# md_builtin_game_v14.net
KiCad netlist of a schematic drawn in EAGLE
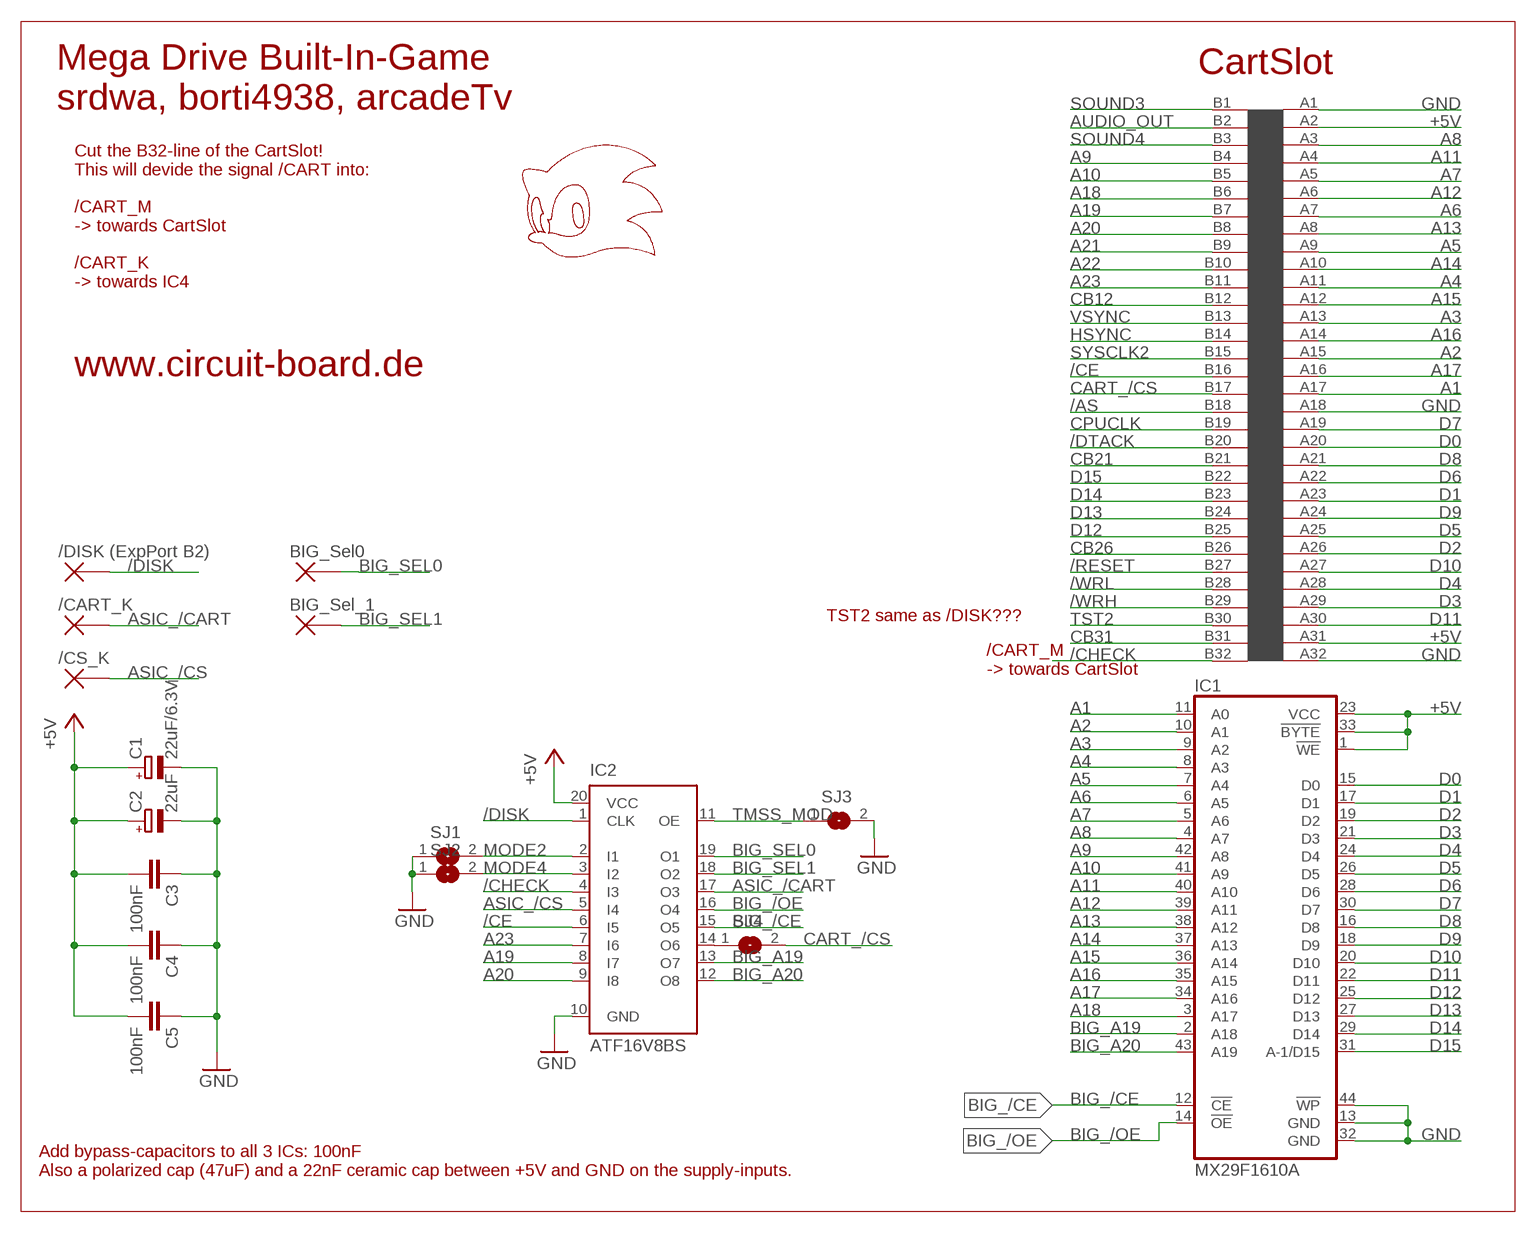
[diagram p0: schematic, sheet 1]

(export (version "E")
  (design (tool "Eeschema 10.0.6"))
  (components
    (comp (ref "C1")
      (value "22uF/6.3V")
      (footprint "eagle-import:SMC_B")
      (libsource (lib "eagle-import") (part "CPOL-EUSMCB"))
    )
    (comp (ref "C2")
      (value "22uF")
      (footprint "eagle-import:SMC_B")
      (libsource (lib "eagle-import") (part "CPOL-EUSMCB"))
    )
    (comp (ref "C3")
      (value "100nF")
      (footprint "eagle-import:Z0805")
      (libsource (lib "eagle-import") (part "C0805"))
    )
    (comp (ref "C4")
      (value "100nF")
      (footprint "eagle-import:Z0805")
      (libsource (lib "eagle-import") (part "C0805"))
    )
    (comp (ref "C5")
      (value "100nF")
      (footprint "eagle-import:Z0805")
      (libsource (lib "eagle-import") (part "C0805"))
    )
    (comp (ref "IC1")
      (value "MX29F1610A")
      (footprint "eagle-import:SO44")
      (libsource (lib "eagle-import") (part "MX29F1610A"))
    )
    (comp (ref "IC2")
      (value "ATF16V8BS")
      (footprint "eagle-import:SO20L")
      (libsource (lib "eagle-import") (part "ATF16V8BS"))
    )
    (comp (ref "SJ1") (value "SJ") (footprint "eagle-import:SJ") (libsource (lib "eagle-import") (part "SJ")))
    (comp (ref "SJ2") (value "SJ") (footprint "eagle-import:SJ") (libsource (lib "eagle-import") (part "SJ")))
    (comp (ref "SJ3") (value "SJ") (footprint "eagle-import:SJ") (libsource (lib "eagle-import") (part "SJ")))
    (comp (ref "SJ4") (value "SJ") (footprint "eagle-import:SJ") (libsource (lib "eagle-import") (part "SJ")))
    (comp (ref "U$1")
      (value "LOGO_SONIC_20MM")
      (footprint "eagle-import:LOGO_SONIC_20MM")
      (libsource (lib "eagle-import") (part "LOGO_SONIC_20MM"))
    )
    (comp (ref "U$2")
      (value "/CS_K")
      (footprint "eagle-import:PADS")
      (libsource (lib "eagle-import") (part "PAD"))
    )
    (comp (ref "U$3")
      (value "/CART_K")
      (footprint "eagle-import:PADS")
      (libsource (lib "eagle-import") (part "PAD"))
    )
    (comp (ref "U$4")
      (value "/DISK (ExpPort B2)")
      (footprint "eagle-import:PADS")
      (libsource (lib "eagle-import") (part "PAD"))
    )
    (comp (ref "U$5")
      (value "BIG_Sel0")
      (footprint "eagle-import:PADS")
      (libsource (lib "eagle-import") (part "PAD"))
    )
    (comp (ref "U$6")
      (value "MEGADRIVE_EDGE_CONNECTOR")
      (footprint "eagle-import:MEGADRIVE_EDGE_CONNECTOR")
      (libsource (lib "eagle-import") (part "MEGADRIVE_EDGE_CONNECTOR"))
    )
    (comp (ref "U$7")
      (value "BIG_Sel_1")
      (footprint "eagle-import:PADS")
      (libsource (lib "eagle-import") (part "PAD"))
    )
  )
  (nets
    (net (code "1") (name "+5V") (class "Default")
      (node (ref "C1") (pin "+") (pinfunction "+_+") (pintype "passive"))
      (node (ref "C2") (pin "+") (pinfunction "+_+") (pintype "passive"))
      (node (ref "C3") (pin "2") (pinfunction "2_2") (pintype "passive"))
      (node (ref "C4") (pin "2") (pinfunction "2_2") (pintype "passive"))
      (node (ref "C5") (pin "2") (pinfunction "2_2") (pintype "passive"))
      (node (ref "IC1") (pin "1") (pinfunction "~{WE}_1") (pintype "input"))
      (node (ref "IC1") (pin "23") (pinfunction "VCC_23") (pintype "output"))
      (node (ref "IC1") (pin "33") (pinfunction "~{BYTE}_33") (pintype "input"))
      (node (ref "IC2") (pin "20") (pinfunction "VCC_20") (pintype "power_in"))
      (node (ref "U$6") (pin "A2") (pinfunction "A2_A2") (pintype "bidirectional"))
      (node (ref "U$6") (pin "A31") (pinfunction "A31_A31") (pintype "bidirectional"))
    )
    (net (code "2") (name "/A1") (class "Default")
      (node (ref "IC1") (pin "11") (pinfunction "A0_11") (pintype "input"))
      (node (ref "U$6") (pin "A17") (pinfunction "A17_A17") (pintype "bidirectional"))
    )
    (net (code "3") (name "/A2") (class "Default")
      (node (ref "IC1") (pin "10") (pinfunction "A1_10") (pintype "input"))
      (node (ref "U$6") (pin "A15") (pinfunction "A15_A15") (pintype "bidirectional"))
    )
    (net (code "4") (name "/A3") (class "Default")
      (node (ref "IC1") (pin "9") (pinfunction "A2_9") (pintype "input"))
      (node (ref "U$6") (pin "A13") (pinfunction "A13_A13") (pintype "bidirectional"))
    )
    (net (code "5") (name "/A4") (class "Default")
      (node (ref "IC1") (pin "8") (pinfunction "A3_8") (pintype "input"))
      (node (ref "U$6") (pin "A11") (pinfunction "A11_A11") (pintype "bidirectional"))
    )
    (net (code "6") (name "/A5") (class "Default")
      (node (ref "IC1") (pin "7") (pinfunction "A4_7") (pintype "input"))
      (node (ref "U$6") (pin "A9") (pinfunction "A9_A9") (pintype "bidirectional"))
    )
    (net (code "7") (name "/A6") (class "Default")
      (node (ref "IC1") (pin "6") (pinfunction "A5_6") (pintype "input"))
      (node (ref "U$6") (pin "A7") (pinfunction "A7_A7") (pintype "bidirectional"))
    )
    (net (code "8") (name "/A7") (class "Default")
      (node (ref "IC1") (pin "5") (pinfunction "A6_5") (pintype "input"))
      (node (ref "U$6") (pin "A5") (pinfunction "A5_A5") (pintype "bidirectional"))
    )
    (net (code "9") (name "/A8") (class "Default")
      (node (ref "IC1") (pin "4") (pinfunction "A7_4") (pintype "input"))
      (node (ref "U$6") (pin "A3") (pinfunction "A3_A3") (pintype "bidirectional"))
    )
    (net (code "10") (name "/A9") (class "Default")
      (node (ref "IC1") (pin "42") (pinfunction "A8_42") (pintype "input"))
      (node (ref "U$6") (pin "B4") (pinfunction "B4_B4") (pintype "bidirectional"))
    )
    (net (code "11") (name "/A10") (class "Default")
      (node (ref "IC1") (pin "41") (pinfunction "A9_41") (pintype "input"))
      (node (ref "U$6") (pin "B5") (pinfunction "B5_B5") (pintype "bidirectional"))
    )
    (net (code "12") (name "/A11") (class "Default")
      (node (ref "IC1") (pin "40") (pinfunction "A10_40") (pintype "input"))
      (node (ref "U$6") (pin "A4") (pinfunction "A4_A4") (pintype "bidirectional"))
    )
    (net (code "13") (name "/A12") (class "Default")
      (node (ref "IC1") (pin "39") (pinfunction "A11_39") (pintype "input"))
      (node (ref "U$6") (pin "A6") (pinfunction "A6_A6") (pintype "bidirectional"))
    )
    (net (code "14") (name "/A13") (class "Default")
      (node (ref "IC1") (pin "38") (pinfunction "A12_38") (pintype "input"))
      (node (ref "U$6") (pin "A8") (pinfunction "A8_A8") (pintype "bidirectional"))
    )
    (net (code "15") (name "/A14") (class "Default")
      (node (ref "IC1") (pin "37") (pinfunction "A13_37") (pintype "input"))
      (node (ref "U$6") (pin "A10") (pinfunction "A10_A10") (pintype "bidirectional"))
    )
    (net (code "16") (name "/A15") (class "Default")
      (node (ref "IC1") (pin "36") (pinfunction "A14_36") (pintype "input"))
      (node (ref "U$6") (pin "A12") (pinfunction "A12_A12") (pintype "bidirectional"))
    )
    (net (code "17") (name "/A16") (class "Default")
      (node (ref "IC1") (pin "35") (pinfunction "A15_35") (pintype "input"))
      (node (ref "U$6") (pin "A14") (pinfunction "A14_A14") (pintype "bidirectional"))
    )
    (net (code "18") (name "/A17") (class "Default")
      (node (ref "IC1") (pin "34") (pinfunction "A16_34") (pintype "input"))
      (node (ref "U$6") (pin "A16") (pinfunction "A16_A16") (pintype "bidirectional"))
    )
    (net (code "19") (name "/A18") (class "Default")
      (node (ref "IC1") (pin "3") (pinfunction "A17_3") (pintype "input"))
      (node (ref "U$6") (pin "B6") (pinfunction "B6_B6") (pintype "bidirectional"))
    )
    (net (code "20") (name "/A19") (class "Default")
      (node (ref "IC2") (pin "8") (pinfunction "I7_8") (pintype "input"))
      (node (ref "U$6") (pin "B7") (pinfunction "B7_B7") (pintype "bidirectional"))
    )
    (net (code "21") (name "/A20") (class "Default")
      (node (ref "IC2") (pin "9") (pinfunction "I8_9") (pintype "input"))
      (node (ref "U$6") (pin "B8") (pinfunction "B8_B8") (pintype "bidirectional"))
    )
    (net (code "22") (name "/A21") (class "Default")
      (node (ref "U$6") (pin "B9") (pinfunction "B9_B9") (pintype "bidirectional"))
    )
    (net (code "23") (name "/A22") (class "Default")
      (node (ref "U$6") (pin "B10") (pinfunction "B10_B10") (pintype "bidirectional"))
    )
    (net (code "24") (name "/A23") (class "Default")
      (node (ref "IC2") (pin "7") (pinfunction "I6_7") (pintype "input"))
      (node (ref "U$6") (pin "B11") (pinfunction "B11_B11") (pintype "bidirectional"))
    )
    (net (code "25") (name "/ASIC_{slash}CART") (class "Default")
      (node (ref "IC2") (pin "17") (pinfunction "O3_17") (pintype "output"))
      (node (ref "U$3") (pin "P$1") (pinfunction "P$1_P$1") (pintype "bidirectional"))
    )
    (net (code "26") (name "/ASIC_{slash}CS") (class "Default")
      (node (ref "IC2") (pin "5") (pinfunction "I4_5") (pintype "input"))
      (node (ref "U$2") (pin "P$1") (pinfunction "P$1_P$1") (pintype "bidirectional"))
    )
    (net (code "27") (name "/AUDIO_OUT") (class "Default")
      (node (ref "U$6") (pin "B2") (pinfunction "B2_B2") (pintype "bidirectional"))
    )
    (net (code "28") (name "/BIG_A19") (class "Default")
      (node (ref "IC1") (pin "2") (pinfunction "A18_2") (pintype "input"))
      (node (ref "IC2") (pin "13") (pinfunction "O7_13") (pintype "output"))
    )
    (net (code "29") (name "/BIG_A20") (class "Default")
      (node (ref "IC1") (pin "43") (pinfunction "A19_43") (pintype "input"))
      (node (ref "IC2") (pin "12") (pinfunction "O8_12") (pintype "output"))
    )
    (net (code "30") (name "/BIG_SEL0") (class "Default")
      (node (ref "IC2") (pin "19") (pinfunction "O1_19") (pintype "output"))
      (node (ref "U$5") (pin "P$1") (pinfunction "P$1_P$1") (pintype "bidirectional"))
    )
    (net (code "31") (name "/BIG_SEL1") (class "Default")
      (node (ref "IC2") (pin "18") (pinfunction "O2_18") (pintype "output"))
      (node (ref "U$7") (pin "P$1") (pinfunction "P$1_P$1") (pintype "bidirectional"))
    )
    (net (code "32") (name "/CART_{slash}CS") (class "Default")
      (node (ref "SJ4") (pin "2") (pinfunction "2_2") (pintype "passive"))
      (node (ref "U$6") (pin "B17") (pinfunction "B17_B17") (pintype "bidirectional"))
    )
    (net (code "33") (name "/CB12") (class "Default")
      (node (ref "U$6") (pin "B12") (pinfunction "B12_B12") (pintype "bidirectional"))
    )
    (net (code "34") (name "/CB21") (class "Default")
      (node (ref "U$6") (pin "B21") (pinfunction "B21_B21") (pintype "bidirectional"))
    )
    (net (code "35") (name "/CB26") (class "Default")
      (node (ref "U$6") (pin "B26") (pinfunction "B26_B26") (pintype "bidirectional"))
    )
    (net (code "36") (name "/CB31") (class "Default")
      (node (ref "U$6") (pin "B31") (pinfunction "B31_B31") (pintype "bidirectional"))
    )
    (net (code "37") (name "/CPUCLK") (class "Default")
      (node (ref "U$6") (pin "B19") (pinfunction "B19_B19") (pintype "bidirectional"))
    )
    (net (code "38") (name "/D0") (class "Default")
      (node (ref "IC1") (pin "15") (pinfunction "D0_15") (pintype "tri_state"))
      (node (ref "U$6") (pin "A20") (pinfunction "A20_A20") (pintype "bidirectional"))
    )
    (net (code "39") (name "/D1") (class "Default")
      (node (ref "IC1") (pin "17") (pinfunction "D1_17") (pintype "tri_state"))
      (node (ref "U$6") (pin "A23") (pinfunction "A23_A23") (pintype "bidirectional"))
    )
    (net (code "40") (name "/D2") (class "Default")
      (node (ref "IC1") (pin "19") (pinfunction "D2_19") (pintype "tri_state"))
      (node (ref "U$6") (pin "A26") (pinfunction "A26_A26") (pintype "bidirectional"))
    )
    (net (code "41") (name "/D3") (class "Default")
      (node (ref "IC1") (pin "21") (pinfunction "D3_21") (pintype "tri_state"))
      (node (ref "U$6") (pin "A29") (pinfunction "A29_A29") (pintype "bidirectional"))
    )
    (net (code "42") (name "/D4") (class "Default")
      (node (ref "IC1") (pin "24") (pinfunction "D4_24") (pintype "tri_state"))
      (node (ref "U$6") (pin "A28") (pinfunction "A28_A28") (pintype "bidirectional"))
    )
    (net (code "43") (name "/D5") (class "Default")
      (node (ref "IC1") (pin "26") (pinfunction "D5_26") (pintype "tri_state"))
      (node (ref "U$6") (pin "A25") (pinfunction "A25_A25") (pintype "bidirectional"))
    )
    (net (code "44") (name "/D6") (class "Default")
      (node (ref "IC1") (pin "28") (pinfunction "D6_28") (pintype "tri_state"))
      (node (ref "U$6") (pin "A22") (pinfunction "A22_A22") (pintype "bidirectional"))
    )
    (net (code "45") (name "/D7") (class "Default")
      (node (ref "IC1") (pin "30") (pinfunction "D7_30") (pintype "tri_state"))
      (node (ref "U$6") (pin "A19") (pinfunction "A19_A19") (pintype "bidirectional"))
    )
    (net (code "46") (name "/D8") (class "Default")
      (node (ref "IC1") (pin "16") (pinfunction "D8_16") (pintype "tri_state"))
      (node (ref "U$6") (pin "A21") (pinfunction "A21_A21") (pintype "bidirectional"))
    )
    (net (code "47") (name "/D9") (class "Default")
      (node (ref "IC1") (pin "18") (pinfunction "D9_18") (pintype "tri_state"))
      (node (ref "U$6") (pin "A24") (pinfunction "A24_A24") (pintype "bidirectional"))
    )
    (net (code "48") (name "/D10") (class "Default")
      (node (ref "IC1") (pin "20") (pinfunction "D10_20") (pintype "tri_state"))
      (node (ref "U$6") (pin "A27") (pinfunction "A27_A27") (pintype "bidirectional"))
    )
    (net (code "49") (name "/D11") (class "Default")
      (node (ref "IC1") (pin "22") (pinfunction "D11_22") (pintype "tri_state"))
      (node (ref "U$6") (pin "A30") (pinfunction "A30_A30") (pintype "bidirectional"))
    )
    (net (code "50") (name "/D12") (class "Default")
      (node (ref "IC1") (pin "25") (pinfunction "D12_25") (pintype "tri_state"))
      (node (ref "U$6") (pin "B25") (pinfunction "B25_B25") (pintype "bidirectional"))
    )
    (net (code "51") (name "/D13") (class "Default")
      (node (ref "IC1") (pin "27") (pinfunction "D13_27") (pintype "tri_state"))
      (node (ref "U$6") (pin "B24") (pinfunction "B24_B24") (pintype "bidirectional"))
    )
    (net (code "52") (name "/D14") (class "Default")
      (node (ref "IC1") (pin "29") (pinfunction "D14_29") (pintype "tri_state"))
      (node (ref "U$6") (pin "B23") (pinfunction "B23_B23") (pintype "bidirectional"))
    )
    (net (code "53") (name "/D15") (class "Default")
      (node (ref "IC1") (pin "31") (pinfunction "A-1/D15_31") (pintype "tri_state"))
      (node (ref "U$6") (pin "B22") (pinfunction "B22_B22") (pintype "bidirectional"))
    )
    (net (code "54") (name "/HSYNC") (class "Default")
      (node (ref "U$6") (pin "B14") (pinfunction "B14_B14") (pintype "bidirectional"))
    )
    (net (code "55") (name "/MODE2") (class "Default")
      (node (ref "IC2") (pin "2") (pinfunction "I1_2") (pintype "input"))
      (node (ref "SJ1") (pin "2") (pinfunction "2_2") (pintype "passive"))
    )
    (net (code "56") (name "/MODE4") (class "Default")
      (node (ref "IC2") (pin "3") (pinfunction "I2_3") (pintype "input"))
      (node (ref "SJ2") (pin "2") (pinfunction "2_2") (pintype "passive"))
    )
    (net (code "57") (name "/SOUND3") (class "Default")
      (node (ref "U$6") (pin "B1") (pinfunction "B1_B1") (pintype "bidirectional"))
    )
    (net (code "58") (name "/SOUND4") (class "Default")
      (node (ref "U$6") (pin "B3") (pinfunction "B3_B3") (pintype "bidirectional"))
    )
    (net (code "59") (name "/SYSCLK2") (class "Default")
      (node (ref "U$6") (pin "B15") (pinfunction "B15_B15") (pintype "bidirectional"))
    )
    (net (code "60") (name "/TMSS_MOD") (class "Default")
      (node (ref "IC2") (pin "11") (pinfunction "OE_11") (pintype "input"))
      (node (ref "SJ3") (pin "1") (pinfunction "1_1") (pintype "passive"))
    )
    (net (code "61") (name "/TST2") (class "Default")
      (node (ref "U$6") (pin "B30") (pinfunction "B30_B30") (pintype "bidirectional"))
    )
    (net (code "62") (name "/VSYNC") (class "Default")
      (node (ref "U$6") (pin "B13") (pinfunction "B13_B13") (pintype "bidirectional"))
    )
    (net (code "63") (name "/{slash}AS") (class "Default")
      (node (ref "U$6") (pin "B18") (pinfunction "B18_B18") (pintype "bidirectional"))
    )
    (net (code "64") (name "/{slash}CE") (class "Default")
      (node (ref "IC2") (pin "6") (pinfunction "I5_6") (pintype "input"))
      (node (ref "U$6") (pin "B16") (pinfunction "B16_B16") (pintype "bidirectional"))
    )
    (net (code "65") (name "/{slash}CHECK") (class "Default")
      (node (ref "IC2") (pin "4") (pinfunction "I3_4") (pintype "input"))
      (node (ref "U$6") (pin "B32") (pinfunction "B32_B32") (pintype "bidirectional"))
    )
    (net (code "66") (name "/{slash}DISK") (class "Default")
      (node (ref "IC2") (pin "1") (pinfunction "CLK_1") (pintype "input"))
      (node (ref "U$4") (pin "P$1") (pinfunction "P$1_P$1") (pintype "bidirectional"))
    )
    (net (code "67") (name "/{slash}DTACK") (class "Default")
      (node (ref "U$6") (pin "B20") (pinfunction "B20_B20") (pintype "bidirectional"))
    )
    (net (code "68") (name "/{slash}RESET") (class "Default")
      (node (ref "U$6") (pin "B27") (pinfunction "B27_B27") (pintype "bidirectional"))
    )
    (net (code "69") (name "/{slash}WRH") (class "Default")
      (node (ref "U$6") (pin "B29") (pinfunction "B29_B29") (pintype "bidirectional"))
    )
    (net (code "70") (name "/{slash}WRL") (class "Default")
      (node (ref "U$6") (pin "B28") (pinfunction "B28_B28") (pintype "bidirectional"))
    )
    (net (code "71") (name "BIG_{slash}CE") (class "Default")
      (node (ref "IC1") (pin "12") (pinfunction "~{CE}_12") (pintype "input"))
      (node (ref "IC2") (pin "15") (pinfunction "O5_15") (pintype "output"))
    )
    (net (code "72") (name "BIG_{slash}OE") (class "Default")
      (node (ref "IC1") (pin "14") (pinfunction "~{OE}_14") (pintype "input"))
      (node (ref "IC2") (pin "16") (pinfunction "O4_16") (pintype "output"))
    )
    (net (code "73") (name "GND") (class "Default")
      (node (ref "C1") (pin "-") (pinfunction "-_-") (pintype "passive"))
      (node (ref "C2") (pin "-") (pinfunction "-_-") (pintype "passive"))
      (node (ref "C3") (pin "1") (pinfunction "1_1") (pintype "passive"))
      (node (ref "C4") (pin "1") (pinfunction "1_1") (pintype "passive"))
      (node (ref "C5") (pin "1") (pinfunction "1_1") (pintype "passive"))
      (node (ref "IC1") (pin "13") (pinfunction "GND_13") (pintype "output"))
      (node (ref "IC1") (pin "32") (pinfunction "GND_32") (pintype "output"))
      (node (ref "IC1") (pin "44") (pinfunction "~{WP}_44") (pintype "output"))
      (node (ref "IC2") (pin "10") (pinfunction "GND_10") (pintype "power_in"))
      (node (ref "SJ1") (pin "1") (pinfunction "1_1") (pintype "passive"))
      (node (ref "SJ2") (pin "1") (pinfunction "1_1") (pintype "passive"))
      (node (ref "SJ3") (pin "2") (pinfunction "2_2") (pintype "passive"))
      (node (ref "U$6") (pin "A1") (pinfunction "A1_A1") (pintype "bidirectional"))
      (node (ref "U$6") (pin "A18") (pinfunction "A18_A18") (pintype "bidirectional"))
      (node (ref "U$6") (pin "A32") (pinfunction "A32_A32") (pintype "bidirectional"))
    )
    (net (code "74") (name "Net-(IC2-O6)") (class "Default")
      (node (ref "IC2") (pin "14") (pinfunction "O6_14") (pintype "output"))
      (node (ref "SJ4") (pin "1") (pinfunction "1_1") (pintype "passive"))
    )
  )
)
